# BANK502.net
KiCad netlist of a schematic drawn in Altium Designer
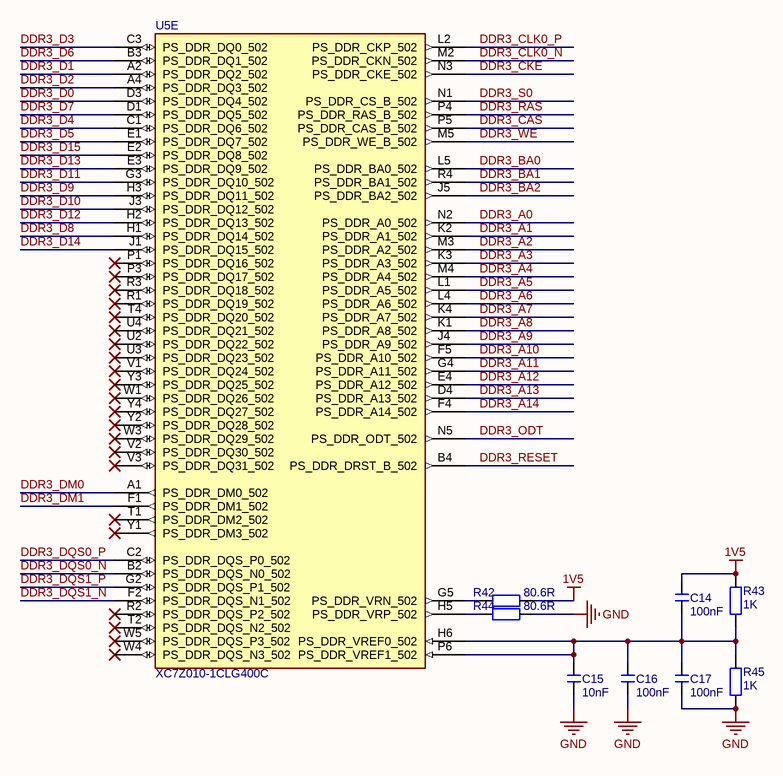
[diagram p0: BANK502.SchDoc]

(export (version "E")
  (design (tool "Eeschema 10.0.6"))
  (components
    (comp (ref "C14")
      (value "100nF")
      (footprint "C 0402_L")
      (description "无极性贴片电容")
      (fields (field (name "版权归属") "源创客"))
      (libsource (lib "3.1   - 电阻-电容-电感") (part "C"))
    )
    (comp (ref "C15")
      (value "10nF")
      (footprint "C 0402_L")
      (description "无极性贴片电容")
      (fields (field (name "版权归属") "源创客"))
      (libsource (lib "3.1   - 电阻-电容-电感") (part "C"))
    )
    (comp (ref "C16")
      (value "100nF")
      (footprint "C 0402_L")
      (description "无极性贴片电容")
      (fields (field (name "版权归属") "源创客"))
      (libsource (lib "3.1   - 电阻-电容-电感") (part "C"))
    )
    (comp (ref "C17")
      (value "100nF")
      (footprint "C 0402_L")
      (description "无极性贴片电容")
      (fields (field (name "版权归属") "源创客"))
      (libsource (lib "3.1   - 电阻-电容-电感") (part "C"))
    )
    (comp (ref "R42")
      (value "80.6R")
      (footprint "R 0805_L")
      (description "贴片电阻")
      (fields (field (name "版权归属") "源创客"))
      (libsource (lib "3.1   - 电阻-电容-电感") (part "R"))
    )
    (comp (ref "R43")
      (value "1K")
      (footprint "R 0402_L")
      (description "贴片电阻")
      (fields (field (name "版权归属") "源创客"))
      (libsource (lib "3.1   - 电阻-电容-电感") (part "R"))
    )
    (comp (ref "R44")
      (value "80.6R")
      (footprint "R 0805_L")
      (description "贴片电阻")
      (fields (field (name "版权归属") "源创客"))
      (libsource (lib "3.1   - 电阻-电容-电感") (part "R"))
    )
    (comp (ref "R45")
      (value "1K")
      (footprint "R 0402_L")
      (description "贴片电阻")
      (fields (field (name "版权归属") "源创客"))
      (libsource (lib "3.1   - 电阻-电容-电感") (part "R"))
    )
    (comp (ref "U5")
      (value "XC7Z010-1CLG400C")
      (footprint "CLG400")
      (description "ZYNQ7000芯片")
      (libsource (lib "16.2 - Xilinx芯片") (part "XC7Z010-1CLG400C"))
    )
  )
  (nets
    (net (code "1") (name "/DDR3_A0") (class "Default")
      (node (ref "U5") (pin "N2") (pinfunction "PS_DDR_A0_502_N2") (pintype "output"))
    )
    (net (code "2") (name "/DDR3_A1") (class "Default")
      (node (ref "U5") (pin "K2") (pinfunction "PS_DDR_A1_502_K2") (pintype "output"))
    )
    (net (code "3") (name "/DDR3_A2") (class "Default")
      (node (ref "U5") (pin "M3") (pinfunction "PS_DDR_A2_502_M3") (pintype "output"))
    )
    (net (code "4") (name "/DDR3_A3") (class "Default")
      (node (ref "U5") (pin "K3") (pinfunction "PS_DDR_A3_502_K3") (pintype "output"))
    )
    (net (code "5") (name "/DDR3_A4") (class "Default")
      (node (ref "U5") (pin "M4") (pinfunction "PS_DDR_A4_502_M4") (pintype "output"))
    )
    (net (code "6") (name "/DDR3_A5") (class "Default")
      (node (ref "U5") (pin "L1") (pinfunction "PS_DDR_A5_502_L1") (pintype "output"))
    )
    (net (code "7") (name "/DDR3_A6") (class "Default")
      (node (ref "U5") (pin "L4") (pinfunction "PS_DDR_A6_502_L4") (pintype "output"))
    )
    (net (code "8") (name "/DDR3_A7") (class "Default")
      (node (ref "U5") (pin "K4") (pinfunction "PS_DDR_A7_502_K4") (pintype "output"))
    )
    (net (code "9") (name "/DDR3_A8") (class "Default")
      (node (ref "U5") (pin "K1") (pinfunction "PS_DDR_A8_502_K1") (pintype "output"))
    )
    (net (code "10") (name "/DDR3_A9") (class "Default")
      (node (ref "U5") (pin "J4") (pinfunction "PS_DDR_A9_502_J4") (pintype "output"))
    )
    (net (code "11") (name "/DDR3_A10") (class "Default")
      (node (ref "U5") (pin "F5") (pinfunction "PS_DDR_A10_502_F5") (pintype "output"))
    )
    (net (code "12") (name "/DDR3_A11") (class "Default")
      (node (ref "U5") (pin "G4") (pinfunction "PS_DDR_A11_502_G4") (pintype "output"))
    )
    (net (code "13") (name "/DDR3_A12") (class "Default")
      (node (ref "U5") (pin "E4") (pinfunction "PS_DDR_A12_502_E4") (pintype "output"))
    )
    (net (code "14") (name "/DDR3_A13") (class "Default")
      (node (ref "U5") (pin "D4") (pinfunction "PS_DDR_A13_502_D4") (pintype "output"))
    )
    (net (code "15") (name "/DDR3_A14") (class "Default")
      (node (ref "U5") (pin "F4") (pinfunction "PS_DDR_A14_502_F4") (pintype "output"))
    )
    (net (code "16") (name "/DDR3_BA0") (class "Default")
      (node (ref "U5") (pin "L5") (pinfunction "PS_DDR_BA0_502_L5") (pintype "output"))
    )
    (net (code "17") (name "/DDR3_BA1") (class "Default")
      (node (ref "U5") (pin "R4") (pinfunction "PS_DDR_BA1_502_R4") (pintype "output"))
    )
    (net (code "18") (name "/DDR3_BA2") (class "Default")
      (node (ref "U5") (pin "J5") (pinfunction "PS_DDR_BA2_502_J5") (pintype "output"))
    )
    (net (code "19") (name "/DDR3_CAS") (class "Default")
      (node (ref "U5") (pin "P5") (pinfunction "PS_DDR_CAS_B_502_P5") (pintype "output"))
    )
    (net (code "20") (name "/DDR3_CKE") (class "Default")
      (node (ref "U5") (pin "N3") (pinfunction "PS_DDR_CKE_502_N3") (pintype "output"))
    )
    (net (code "21") (name "/DDR3_CLK0_N") (class "Default")
      (node (ref "U5") (pin "M2") (pinfunction "PS_DDR_CKN_502_M2") (pintype "output"))
    )
    (net (code "22") (name "/DDR3_CLK0_P") (class "Default")
      (node (ref "U5") (pin "L2") (pinfunction "PS_DDR_CKP_502_L2") (pintype "output"))
    )
    (net (code "23") (name "/DDR3_D0") (class "Default")
      (node (ref "U5") (pin "D3") (pinfunction "PS_DDR_DQ4_502_D3") (pintype "bidirectional"))
    )
    (net (code "24") (name "/DDR3_D1") (class "Default")
      (node (ref "U5") (pin "A2") (pinfunction "PS_DDR_DQ2_502_A2") (pintype "bidirectional"))
    )
    (net (code "25") (name "/DDR3_D2") (class "Default")
      (node (ref "U5") (pin "A4") (pinfunction "PS_DDR_DQ3_502_A4") (pintype "bidirectional"))
    )
    (net (code "26") (name "/DDR3_D3") (class "Default")
      (node (ref "U5") (pin "C3") (pinfunction "PS_DDR_DQ0_502_C3") (pintype "bidirectional"))
    )
    (net (code "27") (name "/DDR3_D4") (class "Default")
      (node (ref "U5") (pin "C1") (pinfunction "PS_DDR_DQ6_502_C1") (pintype "bidirectional"))
    )
    (net (code "28") (name "/DDR3_D5") (class "Default")
      (node (ref "U5") (pin "E1") (pinfunction "PS_DDR_DQ7_502_E1") (pintype "bidirectional"))
    )
    (net (code "29") (name "/DDR3_D6") (class "Default")
      (node (ref "U5") (pin "B3") (pinfunction "PS_DDR_DQ1_502_B3") (pintype "bidirectional"))
    )
    (net (code "30") (name "/DDR3_D7") (class "Default")
      (node (ref "U5") (pin "D1") (pinfunction "PS_DDR_DQ5_502_D1") (pintype "bidirectional"))
    )
    (net (code "31") (name "/DDR3_D8") (class "Default")
      (node (ref "U5") (pin "H1") (pinfunction "PS_DDR_DQ14_502_H1") (pintype "bidirectional"))
    )
    (net (code "32") (name "/DDR3_D9") (class "Default")
      (node (ref "U5") (pin "H3") (pinfunction "PS_DDR_DQ11_502_H3") (pintype "bidirectional"))
    )
    (net (code "33") (name "/DDR3_D10") (class "Default")
      (node (ref "U5") (pin "J3") (pinfunction "PS_DDR_DQ12_502_J3") (pintype "bidirectional"))
    )
    (net (code "34") (name "/DDR3_D11") (class "Default")
      (node (ref "U5") (pin "G3") (pinfunction "PS_DDR_DQ10_502_G3") (pintype "bidirectional"))
    )
    (net (code "35") (name "/DDR3_D12") (class "Default")
      (node (ref "U5") (pin "H2") (pinfunction "PS_DDR_DQ13_502_H2") (pintype "bidirectional"))
    )
    (net (code "36") (name "/DDR3_D13") (class "Default")
      (node (ref "U5") (pin "E3") (pinfunction "PS_DDR_DQ9_502_E3") (pintype "bidirectional"))
    )
    (net (code "37") (name "/DDR3_D14") (class "Default")
      (node (ref "U5") (pin "J1") (pinfunction "PS_DDR_DQ15_502_J1") (pintype "bidirectional"))
    )
    (net (code "38") (name "/DDR3_D15") (class "Default")
      (node (ref "U5") (pin "E2") (pinfunction "PS_DDR_DQ8_502_E2") (pintype "bidirectional"))
    )
    (net (code "39") (name "/DDR3_DM0") (class "Default")
      (node (ref "U5") (pin "A1") (pinfunction "PS_DDR_DM0_502_A1") (pintype "output"))
    )
    (net (code "40") (name "/DDR3_DM1") (class "Default")
      (node (ref "U5") (pin "F1") (pinfunction "PS_DDR_DM1_502_F1") (pintype "output"))
    )
    (net (code "41") (name "/DDR3_DQS0_N") (class "Default")
      (node (ref "U5") (pin "B2") (pinfunction "PS_DDR_DQS_N0_502_B2") (pintype "bidirectional"))
    )
    (net (code "42") (name "/DDR3_DQS0_P") (class "Default")
      (node (ref "U5") (pin "C2") (pinfunction "PS_DDR_DQS_P0_502_C2") (pintype "bidirectional"))
    )
    (net (code "43") (name "/DDR3_DQS1_N") (class "Default")
      (node (ref "U5") (pin "F2") (pinfunction "PS_DDR_DQS_N1_502_F2") (pintype "bidirectional"))
    )
    (net (code "44") (name "/DDR3_DQS1_P") (class "Default")
      (node (ref "U5") (pin "G2") (pinfunction "PS_DDR_DQS_P1_502_G2") (pintype "bidirectional"))
    )
    (net (code "45") (name "/DDR3_ODT") (class "Default")
      (node (ref "U5") (pin "N5") (pinfunction "PS_DDR_ODT_502_N5") (pintype "output"))
    )
    (net (code "46") (name "/DDR3_RAS") (class "Default")
      (node (ref "U5") (pin "P4") (pinfunction "PS_DDR_RAS_B_502_P4") (pintype "output"))
    )
    (net (code "47") (name "/DDR3_RESET") (class "Default")
      (node (ref "U5") (pin "B4") (pinfunction "PS_DDR_DRST_B_502_B4") (pintype "output"))
    )
    (net (code "48") (name "/DDR3_S0") (class "Default")
      (node (ref "U5") (pin "N1") (pinfunction "PS_DDR_CS_B_502_N1") (pintype "output"))
    )
    (net (code "49") (name "/DDR3_WE") (class "Default")
      (node (ref "U5") (pin "M5") (pinfunction "PS_DDR_WE_B_502_M5") (pintype "output"))
    )
    (net (code "50") (name "1V5") (class "Default")
      (node (ref "C14") (pin "2") (pinfunction "2_2") (pintype "passive"))
      (node (ref "R42") (pin "2") (pinfunction "2_2") (pintype "passive"))
      (node (ref "R43") (pin "1") (pinfunction "1_1") (pintype "passive"))
    )
    (net (code "51") (name "GND") (class "Default")
      (node (ref "C15") (pin "1") (pinfunction "1_1") (pintype "passive"))
      (node (ref "C16") (pin "1") (pinfunction "1_1") (pintype "passive"))
      (node (ref "C17") (pin "1") (pinfunction "1_1") (pintype "passive"))
      (node (ref "R44") (pin "2") (pinfunction "2_2") (pintype "passive"))
      (node (ref "R45") (pin "2") (pinfunction "2_2") (pintype "passive"))
    )
    (net (code "52") (name "Net-(U5E-PS_DDR_VREF0_502)") (class "Default")
      (node (ref "C14") (pin "1") (pinfunction "1_1") (pintype "passive"))
      (node (ref "C15") (pin "2") (pinfunction "2_2") (pintype "passive"))
      (node (ref "C16") (pin "2") (pinfunction "2_2") (pintype "passive"))
      (node (ref "C17") (pin "2") (pinfunction "2_2") (pintype "passive"))
      (node (ref "R43") (pin "2") (pinfunction "2_2") (pintype "passive"))
      (node (ref "R45") (pin "1") (pinfunction "1_1") (pintype "passive"))
      (node (ref "U5") (pin "H6") (pinfunction "PS_DDR_VREF0_502_H6") (pintype "input"))
      (node (ref "U5") (pin "P6") (pinfunction "PS_DDR_VREF1_502_P6") (pintype "input"))
    )
    (net (code "53") (name "Net-(U5E-PS_DDR_VRN_502)") (class "Default")
      (node (ref "R42") (pin "1") (pinfunction "1_1") (pintype "passive"))
      (node (ref "U5") (pin "G5") (pinfunction "PS_DDR_VRN_502_G5") (pintype "output"))
    )
    (net (code "54") (name "Net-(U5E-PS_DDR_VRP_502)") (class "Default")
      (node (ref "R44") (pin "1") (pinfunction "1_1") (pintype "passive"))
      (node (ref "U5") (pin "H5") (pinfunction "PS_DDR_VRP_502_H5") (pintype "output"))
    )
    (net (code "55") (name "unconnected-(U5E-PS_DDR_DM2_502-PadT1)") (class "Default")
      (node (ref "U5") (pin "T1") (pinfunction "PS_DDR_DM2_502_T1") (pintype "output+no_connect"))
    )
    (net (code "56") (name "unconnected-(U5E-PS_DDR_DM3_502-PadY1)") (class "Default")
      (node (ref "U5") (pin "Y1") (pinfunction "PS_DDR_DM3_502_Y1") (pintype "output+no_connect"))
    )
    (net (code "57") (name "unconnected-(U5E-PS_DDR_DQ16_502-PadP1)") (class "Default")
      (node (ref "U5") (pin "P1") (pinfunction "PS_DDR_DQ16_502_P1") (pintype "bidirectional+no_connect"))
    )
    (net (code "58") (name "unconnected-(U5E-PS_DDR_DQ17_502-PadP3)") (class "Default")
      (node (ref "U5") (pin "P3") (pinfunction "PS_DDR_DQ17_502_P3") (pintype "bidirectional+no_connect"))
    )
    (net (code "59") (name "unconnected-(U5E-PS_DDR_DQ18_502-PadR3)") (class "Default")
      (node (ref "U5") (pin "R3") (pinfunction "PS_DDR_DQ18_502_R3") (pintype "bidirectional+no_connect"))
    )
    (net (code "60") (name "unconnected-(U5E-PS_DDR_DQ19_502-PadR1)") (class "Default")
      (node (ref "U5") (pin "R1") (pinfunction "PS_DDR_DQ19_502_R1") (pintype "bidirectional+no_connect"))
    )
    (net (code "61") (name "unconnected-(U5E-PS_DDR_DQ20_502-PadT4)") (class "Default")
      (node (ref "U5") (pin "T4") (pinfunction "PS_DDR_DQ20_502_T4") (pintype "bidirectional+no_connect"))
    )
    (net (code "62") (name "unconnected-(U5E-PS_DDR_DQ21_502-PadU4)") (class "Default")
      (node (ref "U5") (pin "U4") (pinfunction "PS_DDR_DQ21_502_U4") (pintype "bidirectional+no_connect"))
    )
    (net (code "63") (name "unconnected-(U5E-PS_DDR_DQ22_502-PadU2)") (class "Default")
      (node (ref "U5") (pin "U2") (pinfunction "PS_DDR_DQ22_502_U2") (pintype "bidirectional+no_connect"))
    )
    (net (code "64") (name "unconnected-(U5E-PS_DDR_DQ23_502-PadU3)") (class "Default")
      (node (ref "U5") (pin "U3") (pinfunction "PS_DDR_DQ23_502_U3") (pintype "bidirectional+no_connect"))
    )
    (net (code "65") (name "unconnected-(U5E-PS_DDR_DQ24_502-PadV1)") (class "Default")
      (node (ref "U5") (pin "V1") (pinfunction "PS_DDR_DQ24_502_V1") (pintype "bidirectional+no_connect"))
    )
    (net (code "66") (name "unconnected-(U5E-PS_DDR_DQ25_502-PadY3)") (class "Default")
      (node (ref "U5") (pin "Y3") (pinfunction "PS_DDR_DQ25_502_Y3") (pintype "bidirectional+no_connect"))
    )
    (net (code "67") (name "unconnected-(U5E-PS_DDR_DQ26_502-PadW1)") (class "Default")
      (node (ref "U5") (pin "W1") (pinfunction "PS_DDR_DQ26_502_W1") (pintype "bidirectional+no_connect"))
    )
    (net (code "68") (name "unconnected-(U5E-PS_DDR_DQ27_502-PadY4)") (class "Default")
      (node (ref "U5") (pin "Y4") (pinfunction "PS_DDR_DQ27_502_Y4") (pintype "bidirectional+no_connect"))
    )
    (net (code "69") (name "unconnected-(U5E-PS_DDR_DQ28_502-PadY2)") (class "Default")
      (node (ref "U5") (pin "Y2") (pinfunction "PS_DDR_DQ28_502_Y2") (pintype "bidirectional+no_connect"))
    )
    (net (code "70") (name "unconnected-(U5E-PS_DDR_DQ29_502-PadW3)") (class "Default")
      (node (ref "U5") (pin "W3") (pinfunction "PS_DDR_DQ29_502_W3") (pintype "bidirectional+no_connect"))
    )
    (net (code "71") (name "unconnected-(U5E-PS_DDR_DQ30_502-PadV2)") (class "Default")
      (node (ref "U5") (pin "V2") (pinfunction "PS_DDR_DQ30_502_V2") (pintype "bidirectional+no_connect"))
    )
    (net (code "72") (name "unconnected-(U5E-PS_DDR_DQ31_502-PadV3)") (class "Default")
      (node (ref "U5") (pin "V3") (pinfunction "PS_DDR_DQ31_502_V3") (pintype "bidirectional+no_connect"))
    )
    (net (code "73") (name "unconnected-(U5E-PS_DDR_DQS_N2_502-PadT2)") (class "Default")
      (node (ref "U5") (pin "T2") (pinfunction "PS_DDR_DQS_N2_502_T2") (pintype "bidirectional+no_connect"))
    )
    (net (code "74") (name "unconnected-(U5E-PS_DDR_DQS_N3_502-PadW4)") (class "Default")
      (node (ref "U5") (pin "W4") (pinfunction "PS_DDR_DQS_N3_502_W4") (pintype "bidirectional+no_connect"))
    )
    (net (code "75") (name "unconnected-(U5E-PS_DDR_DQS_P2_502-PadR2)") (class "Default")
      (node (ref "U5") (pin "R2") (pinfunction "PS_DDR_DQS_P2_502_R2") (pintype "bidirectional+no_connect"))
    )
    (net (code "76") (name "unconnected-(U5E-PS_DDR_DQS_P3_502-PadW5)") (class "Default")
      (node (ref "U5") (pin "W5") (pinfunction "PS_DDR_DQS_P3_502_W5") (pintype "bidirectional+no_connect"))
    )
  )
)
